# Si4010_Beacon_Adjusted.net
KiCad netlist of a schematic drawn in Altium Designer
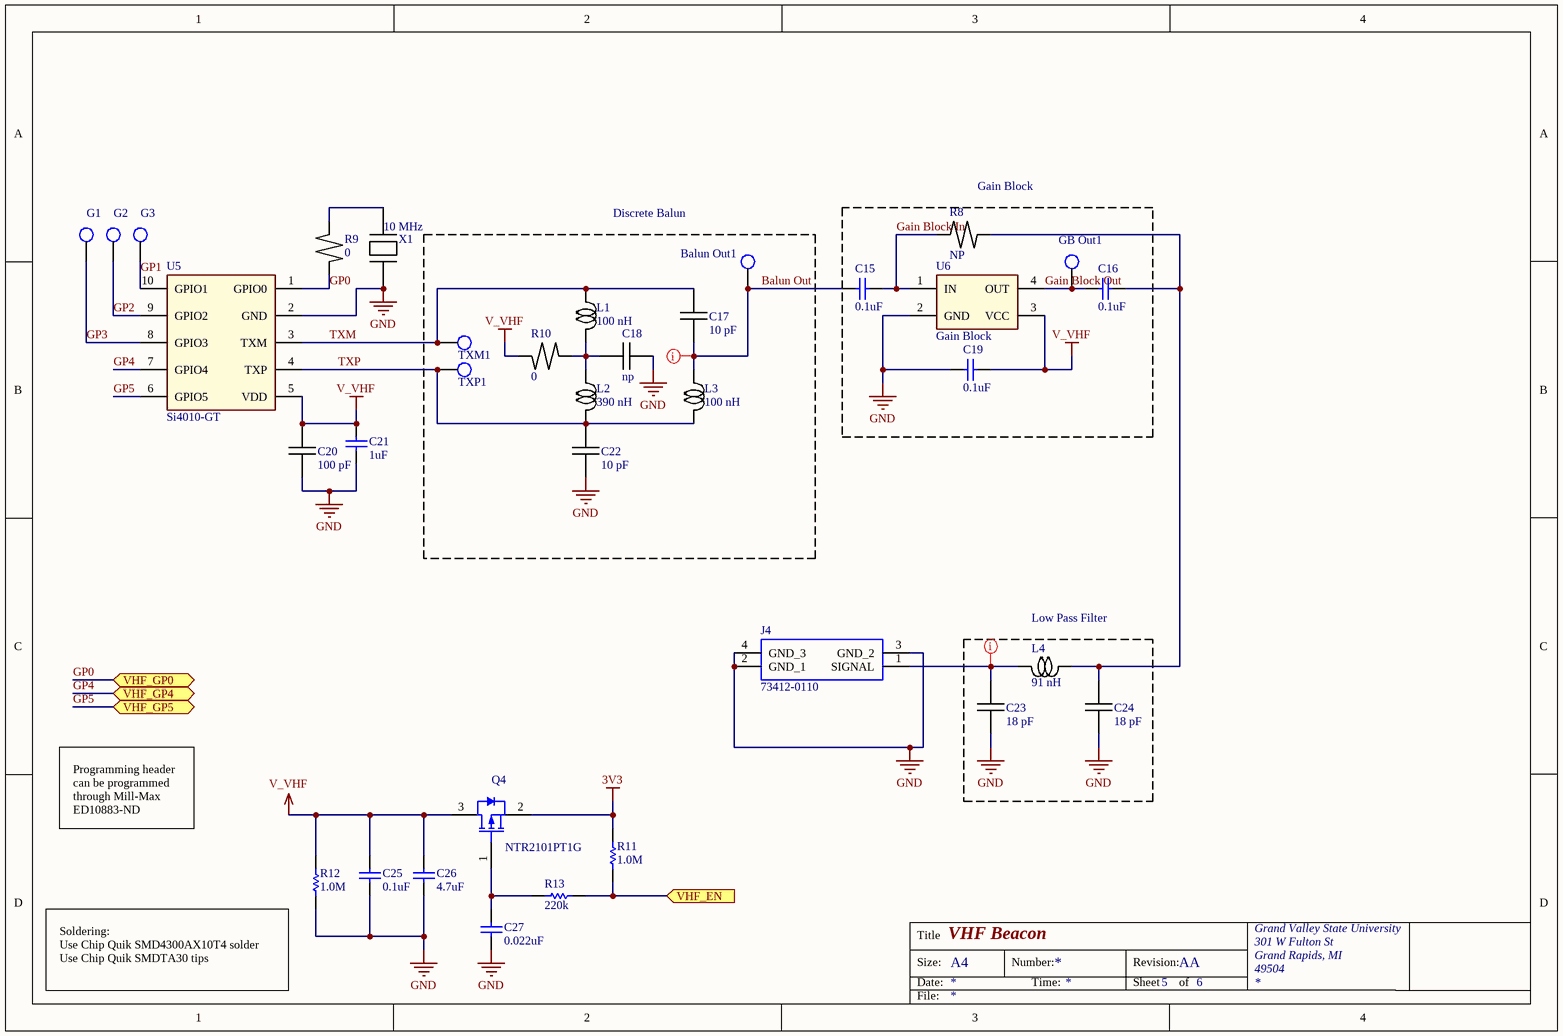
[diagram p0: Si4010 Beacon Adjusted.SchDoc]

(export (version "E")
  (design (tool "Eeschema 10.0.6"))
  (components
    (comp (ref "Balun Out1")
      (value "Test Point")
      (footprint "Test Point-SM35")
      (libsource (lib "VHF Library") (part "Test Point"))
    )
    (comp (ref "C15")
      (value "0.1uF")
      (footprint "0402cap")
      (description "0402 Ceramic Chip Capacitor - Standard")
      (fields (field (name "Comment") "C0402"))
      (libsource (lib "lib-Standard") (part "C0402"))
    )
    (comp (ref "C16")
      (value "0.1uF")
      (footprint "0402cap")
      (description "0402 Ceramic Chip Capacitor - Standard")
      (fields (field (name "Comment") "C0402"))
      (libsource (lib "lib-Standard") (part "C0402"))
    )
    (comp (ref "C17")
      (value "10 pF")
      (footprint "Capacitor - 0402")
      (description "Chip Capacitor")
      (libsource (lib "VHF Library") (part "Chip Capacitor"))
    )
    (comp (ref "C18")
      (value "np")
      (footprint "Capacitor - 0402")
      (description "Chip Capacitor")
      (libsource (lib "VHF Library") (part "Chip Capacitor"))
    )
    (comp (ref "C19")
      (value "0.1uF")
      (footprint "0402cap")
      (description "0402 Ceramic Chip Capacitor - Standard")
      (fields (field (name "Comment") "C0402"))
      (libsource (lib "lib-Standard") (part "C0402"))
    )
    (comp (ref "C20")
      (value "100 pF")
      (footprint "Capacitor - 0402")
      (description "Chip Capacitor")
      (libsource (lib "VHF Library") (part "Chip Capacitor"))
    )
    (comp (ref "C21")
      (value "1uF")
      (footprint "0402cap")
      (description "0402 Ceramic Chip Capacitor - Standard")
      (fields (field (name "Comment") "C0402"))
      (libsource (lib "Chip Capacitor") (part "C0402"))
    )
    (comp (ref "C22")
      (value "10 pF")
      (footprint "Capacitor - 0402")
      (description "Chip Capacitor")
      (libsource (lib "VHF Library") (part "Chip Capacitor"))
    )
    (comp (ref "C23")
      (value "18 pF")
      (footprint "Capacitor - 0402")
      (description "Chip Capacitor")
      (libsource (lib "VHF Library") (part "Chip Capacitor"))
    )
    (comp (ref "C24")
      (value "18 pF")
      (footprint "Capacitor - 0402")
      (description "Chip Capacitor")
      (libsource (lib "VHF Library") (part "Chip Capacitor"))
    )
    (comp (ref "C25")
      (value "0.1uF")
      (footprint "0402cap")
      (description "0402 Ceramic Chip Capacitor - Standard")
      (fields (field (name "Comment") "C0402"))
      (libsource (lib "lib-Standard") (part "C0402"))
    )
    (comp (ref "C26")
      (value "4.7uF")
      (footprint "0603CAP")
      (description "0603 Ceramic Chip Capacitor - Standard")
      (fields (field (name "Comment") "C0603"))
      (libsource (lib "lib-Standard") (part "C0603"))
    )
    (comp (ref "C27")
      (value "0.022uF")
      (footprint "0402cap")
      (description "0402 Ceramic Chip Capacitor - Standard")
      (fields (field (name "Comment") "C0402"))
      (libsource (lib "lib-Standard") (part "C0402"))
    )
    (comp (ref "G1")
      (value "Test Point")
      (footprint "Test Point-SM55")
      (libsource (lib "VHF Library") (part "Test Point"))
    )
    (comp (ref "G2")
      (value "Test Point")
      (footprint "Test Point-SM55")
      (libsource (lib "VHF Library") (part "Test Point"))
    )
    (comp (ref "G3")
      (value "Test Point")
      (footprint "Test Point-SM55")
      (libsource (lib "VHF Library") (part "Test Point"))
    )
    (comp (ref "GB Out1")
      (value "Test Point")
      (footprint "Test Point-SM35")
      (libsource (lib "VHF Library") (part "Test Point"))
    )
    (comp (ref "J4")
      (value "73412-0110")
      (footprint "73412-0110")
      (description "50 Ohms, MCRF, PCB Vertical Jack Receptacle, SMT, 1.25mm Mounted Height")
      (fields (field (name "RS PART NUMBER") "1676350") (field (name "MOUSER PART NUMBER") "538-73412-0110"))
      (libsource (lib "lib-Connectors") (part "73412-0110"))
    )
    (comp (ref "L1")
      (value "100 nH")
      (footprint "Inductor - 0402")
      (description "0402 Inductor")
      (fields (field (name "Comment") "0402"))
      (libsource (lib "VHF Library") (part "Inductor - 0402"))
    )
    (comp (ref "L2")
      (value "390 nH")
      (footprint "Inductor - 0402")
      (description "0402 Inductor")
      (fields (field (name "Comment") "0402"))
      (libsource (lib "VHF Library") (part "Inductor - 0402"))
    )
    (comp (ref "L3")
      (value "100 nH")
      (footprint "Inductor - 0402")
      (description "0402 Inductor")
      (fields (field (name "Comment") "0402"))
      (libsource (lib "VHF Library") (part "Inductor - 0402"))
    )
    (comp (ref "L4")
      (value "91 nH")
      (footprint "Inductor - 0402")
      (description "0402 Inductor")
      (fields (field (name "Comment") "0402"))
      (libsource (lib "") (part "Inductor - 0402_1"))
    )
    (comp (ref "Q4")
      (value "NTR2101PT1G")
      (footprint "ONSC-SOT-23-3-318-08_V")
      (description "Small Signal MOSFET, -8 V, -3.7 A, Single P-Channel, 3-Pin SOT-23, Pb-Free, Tape and Reel")
      (libsource (lib "ON Semi MOSFETs") (part "NTR2101PT1G"))
    )
    (comp (ref "R8")
      (value "NP")
      (footprint "Resistor - 0402")
      (description "Chip Resistor")
      (libsource (lib "VHF Library") (part "Chip Resistor"))
    )
    (comp (ref "R9")
      (value "0")
      (footprint "Resistor - 0402")
      (description "Chip Resistor")
      (libsource (lib "VHF Library") (part "Chip Resistor"))
    )
    (comp (ref "R10")
      (value "0")
      (footprint "Resistor - 0402")
      (description "Chip Resistor")
      (libsource (lib "VHF Library") (part "Chip Resistor"))
    )
    (comp (ref "R11")
      (value "1.0M")
      (footprint "0402RES")
      (description "0402 Chip Resistor - Standard")
      (fields (field (name "Comment") "R0402"))
      (libsource (lib "lib-Standard") (part "R0402"))
    )
    (comp (ref "R12")
      (value "1.0M")
      (footprint "0402RES")
      (description "0402 Chip Resistor - Standard")
      (fields (field (name "Comment") "R0402"))
      (libsource (lib "lib-Standard") (part "R0402"))
    )
    (comp (ref "R13")
      (value "220k")
      (footprint "0402RES")
      (description "0402 Chip Resistor - Standard")
      (fields (field (name "Comment") "R0402"))
      (libsource (lib "lib-Standard") (part "R0402"))
    )
    (comp (ref "TXM1")
      (value "Test Point")
      (footprint "Test Point-SM35")
      (libsource (lib "VHF Library") (part "Test Point"))
    )
    (comp (ref "TXP1")
      (value "Test Point")
      (footprint "Test Point-SM35")
      (libsource (lib "VHF Library") (part "Test Point"))
    )
    (comp (ref "U5")
      (value "Si4010-GT")
      (footprint "MSOP10")
      (description "Transmitter/MCU")
      (fields (field (name "MANUFACTURER") "Silion Labs"))
      (libsource (lib "VHF Library") (part "Si4010-GT"))
    )
    (comp (ref "U6")
      (value "Gain Block")
      (footprint "BGA427")
      (fields (field (name "MANUFACTURER") "Infineon"))
      (libsource (lib "VHF Library") (part "BGA427"))
    )
    (comp (ref "X1")
      (value "10 MHz")
      (footprint "ECS Crystal")
      (fields (field (name "MANUFACTURER") "ECS") (field (name "Comment") "Crystal"))
      (libsource (lib "VHF Library") (part "ECS 53B Crystal"))
    )
  )
  (nets
    (net (code "1") (name "/Balun Out") (class "Default")
      (node (ref "Balun Out1") (pin "1") (pinfunction "1_1") (pintype "passive"))
      (node (ref "C15") (pin "1") (pinfunction "1_1") (pintype "passive"))
      (node (ref "C17") (pin "1") (pinfunction "1_1") (pintype "passive"))
      (node (ref "L3") (pin "1") (pinfunction "1_1") (pintype "passive"))
    )
    (net (code "2") (name "/GP0") (class "Default")
      (node (ref "R9") (pin "2") (pinfunction "2_2") (pintype "passive"))
      (node (ref "U5") (pin "1") (pinfunction "GPIO0_1") (pintype "passive"))
    )
    (net (code "3") (name "/GP1") (class "Default")
      (node (ref "G3") (pin "1") (pinfunction "1_1") (pintype "passive"))
      (node (ref "U5") (pin "10") (pinfunction "GPIO1_10") (pintype "passive"))
    )
    (net (code "4") (name "/GP2") (class "Default")
      (node (ref "G2") (pin "1") (pinfunction "1_1") (pintype "passive"))
      (node (ref "U5") (pin "9") (pinfunction "GPIO2_9") (pintype "passive"))
    )
    (net (code "5") (name "/GP3") (class "Default")
      (node (ref "G1") (pin "1") (pinfunction "1_1") (pintype "passive"))
      (node (ref "U5") (pin "8") (pinfunction "GPIO3_8") (pintype "passive"))
    )
    (net (code "6") (name "/GP4") (class "Default")
      (node (ref "U5") (pin "7") (pinfunction "GPIO4_7") (pintype "passive"))
    )
    (net (code "7") (name "/GP5") (class "Default")
      (node (ref "U5") (pin "6") (pinfunction "GPIO5_6") (pintype "passive"))
    )
    (net (code "8") (name "/Gain Block In") (class "Default")
      (node (ref "C15") (pin "2") (pinfunction "2_2") (pintype "passive"))
      (node (ref "R8") (pin "1") (pinfunction "1_1") (pintype "passive"))
      (node (ref "U6") (pin "1") (pinfunction "IN_1") (pintype "passive"))
    )
    (net (code "9") (name "/Gain Block Out") (class "Default")
      (node (ref "C16") (pin "1") (pinfunction "1_1") (pintype "passive"))
      (node (ref "GB Out1") (pin "1") (pinfunction "1_1") (pintype "passive"))
      (node (ref "U6") (pin "4") (pinfunction "OUT_4") (pintype "passive"))
    )
    (net (code "10") (name "/TXM") (class "Default")
      (node (ref "C17") (pin "2") (pinfunction "2_2") (pintype "passive"))
      (node (ref "L1") (pin "1") (pinfunction "1_1") (pintype "passive"))
      (node (ref "TXM1") (pin "1") (pinfunction "1_1") (pintype "passive"))
      (node (ref "U5") (pin "3") (pinfunction "TXM_3") (pintype "passive"))
    )
    (net (code "11") (name "/TXP") (class "Default")
      (node (ref "C22") (pin "2") (pinfunction "2_2") (pintype "passive"))
      (node (ref "L2") (pin "2") (pinfunction "2_2") (pintype "passive"))
      (node (ref "L3") (pin "2") (pinfunction "2_2") (pintype "passive"))
      (node (ref "TXP1") (pin "1") (pinfunction "1_1") (pintype "passive"))
      (node (ref "U5") (pin "4") (pinfunction "TXP_4") (pintype "passive"))
    )
    (net (code "12") (name "/VHF_EN") (class "Default")
      (node (ref "R11") (pin "1") (pinfunction "1_1") (pintype "passive"))
      (node (ref "R13") (pin "1") (pinfunction "1_1") (pintype "passive"))
    )
    (net (code "13") (name "3V3") (class "Default")
      (node (ref "Q4") (pin "2") (pinfunction "S_2") (pintype "passive"))
      (node (ref "R11") (pin "2") (pinfunction "2_2") (pintype "passive"))
    )
    (net (code "14") (name "GND") (class "Default")
      (node (ref "C18") (pin "1") (pinfunction "1_1") (pintype "passive"))
      (node (ref "C19") (pin "1") (pinfunction "1_1") (pintype "passive"))
      (node (ref "C20") (pin "2") (pinfunction "2_2") (pintype "passive"))
      (node (ref "C21") (pin "1") (pinfunction "1_1") (pintype "passive"))
      (node (ref "C22") (pin "1") (pinfunction "1_1") (pintype "passive"))
      (node (ref "C23") (pin "2") (pinfunction "2_2") (pintype "passive"))
      (node (ref "C24") (pin "2") (pinfunction "2_2") (pintype "passive"))
      (node (ref "C25") (pin "1") (pinfunction "1_1") (pintype "passive"))
      (node (ref "C26") (pin "1") (pinfunction "1_1") (pintype "passive"))
      (node (ref "C27") (pin "1") (pinfunction "1_1") (pintype "passive"))
      (node (ref "J4") (pin "2") (pinfunction "GND_1_2") (pintype "passive"))
      (node (ref "J4") (pin "3") (pinfunction "GND_2_3") (pintype "passive"))
      (node (ref "J4") (pin "4") (pinfunction "GND_3_4") (pintype "passive"))
      (node (ref "R12") (pin "1") (pinfunction "1_1") (pintype "passive"))
      (node (ref "U5") (pin "2") (pinfunction "GND_2") (pintype "passive"))
      (node (ref "U6") (pin "2") (pinfunction "GND_2") (pintype "passive"))
      (node (ref "X1") (pin "1") (pinfunction "1_1") (pintype "passive"))
    )
    (net (code "15") (name "Net-(C16-Pad2)") (class "Default")
      (node (ref "C16") (pin "2") (pinfunction "2_2") (pintype "passive"))
      (node (ref "C24") (pin "1") (pinfunction "1_1") (pintype "passive"))
      (node (ref "L4") (pin "2") (pinfunction "2_2") (pintype "passive"))
      (node (ref "R8") (pin "2") (pinfunction "2_2") (pintype "passive"))
    )
    (net (code "16") (name "Net-(C18-Pad2)") (class "Default")
      (node (ref "C18") (pin "2") (pinfunction "2_2") (pintype "passive"))
      (node (ref "L1") (pin "2") (pinfunction "2_2") (pintype "passive"))
      (node (ref "L2") (pin "1") (pinfunction "1_1") (pintype "passive"))
      (node (ref "R10") (pin "2") (pinfunction "2_2") (pintype "passive"))
    )
    (net (code "17") (name "Net-(J4-SIGNAL)") (class "Default")
      (node (ref "C23") (pin "1") (pinfunction "1_1") (pintype "passive"))
      (node (ref "J4") (pin "1") (pinfunction "SIGNAL_1") (pintype "passive"))
      (node (ref "L4") (pin "1") (pinfunction "1_1") (pintype "passive"))
    )
    (net (code "18") (name "Net-(Q4-G)") (class "Default")
      (node (ref "C27") (pin "2") (pinfunction "2_2") (pintype "passive"))
      (node (ref "Q4") (pin "1") (pinfunction "G_1") (pintype "passive"))
      (node (ref "R13") (pin "2") (pinfunction "2_2") (pintype "passive"))
    )
    (net (code "19") (name "Net-(R9-Pad1)") (class "Default")
      (node (ref "R9") (pin "1") (pinfunction "1_1") (pintype "passive"))
      (node (ref "X1") (pin "3") (pinfunction "3_3") (pintype "passive"))
    )
    (net (code "20") (name "V_VHF") (class "Default")
      (node (ref "C19") (pin "2") (pinfunction "2_2") (pintype "passive"))
      (node (ref "C20") (pin "1") (pinfunction "1_1") (pintype "passive"))
      (node (ref "C21") (pin "2") (pinfunction "2_2") (pintype "passive"))
      (node (ref "C25") (pin "2") (pinfunction "2_2") (pintype "passive"))
      (node (ref "C26") (pin "2") (pinfunction "2_2") (pintype "passive"))
      (node (ref "Q4") (pin "3") (pinfunction "D_3") (pintype "passive"))
      (node (ref "R10") (pin "1") (pinfunction "1_1") (pintype "passive"))
      (node (ref "R12") (pin "2") (pinfunction "2_2") (pintype "passive"))
      (node (ref "U5") (pin "5") (pinfunction "VDD_5") (pintype "passive"))
      (node (ref "U6") (pin "3") (pinfunction "VCC_3") (pintype "passive"))
    )
  )
)
